# BuckConverter.net
KiCad netlist of a schematic drawn in Altium Designer
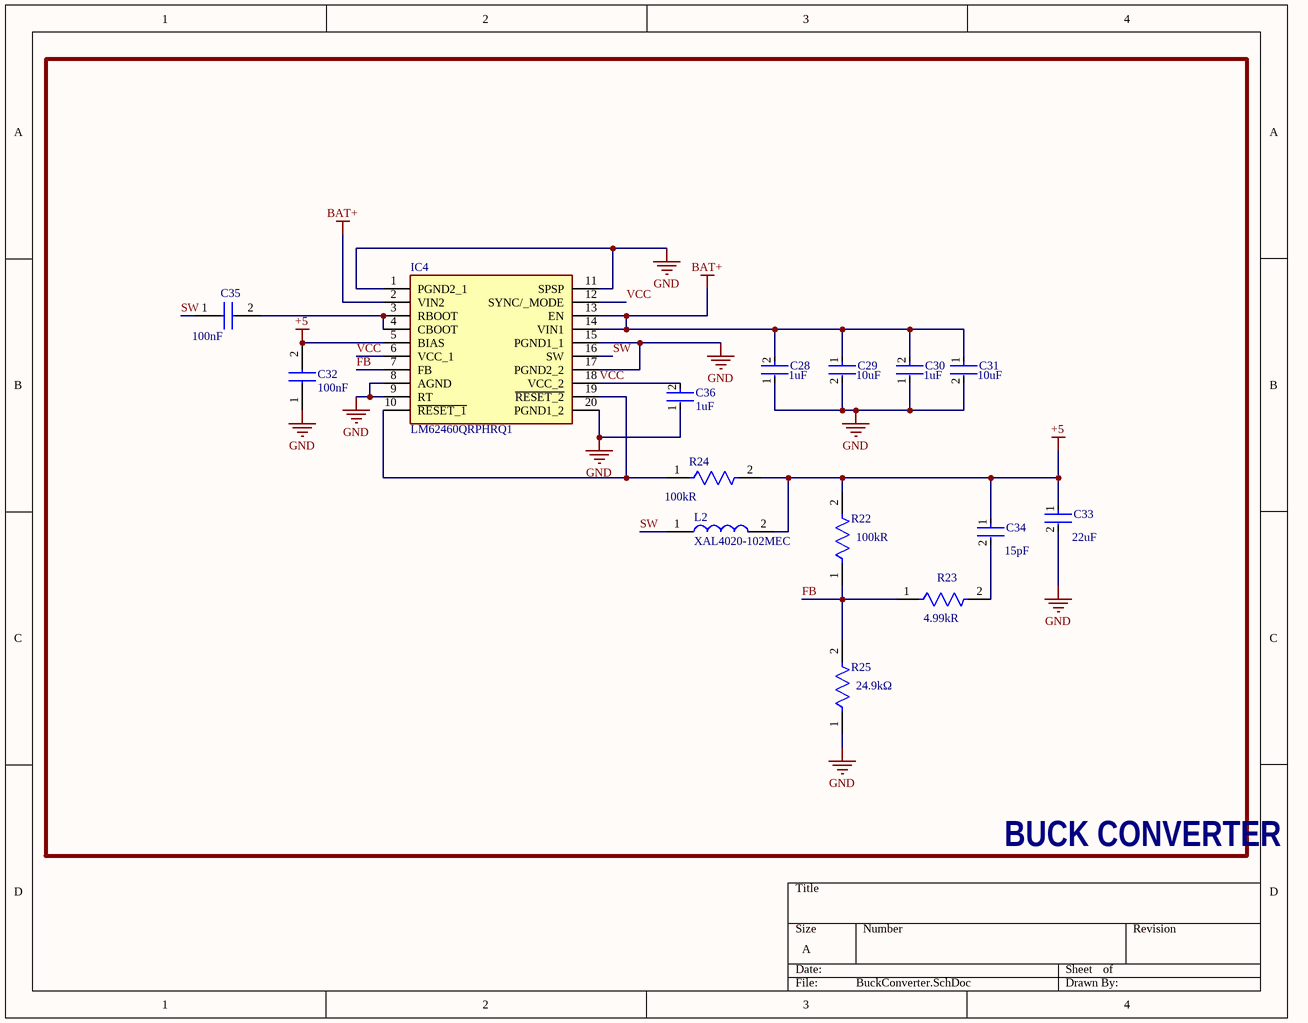
[diagram p0: BuckConverter.SchDoc]

(export (version "E")
  (design (tool "Eeschema 10.0.6"))
  (components
    (comp (ref "C28")
      (value "C1608X5R1H105K080AB")
      (footprint "FP-C1608-080-0_1-IPC_B")
      (description "Multilayer Ceramic Capacitors 1μF ±10% 50V X5R SMD 0603")
      (fields
        (field (name "VOLTAGE") "50V")
        (field (name "CAPACITANCE") "1uF")
        (field (name "TOLERANCE") "10%")
      )
      (libsource (lib "Altium Content Vault") (part "236180d848d6139a670b325ea6854c9"))
    )
    (comp (ref "C29")
      (value "GRM32ER71H106KA12L")
      (footprint "FP-GRM32-MFG")
      (description "CAP CER 10UF 50V X7R 1210")
      (fields
        (field (name "TOLERANCE") "10%")
        (field (name "MANUFACTURER") "Murata")
        (field (name "CAPACITANCE") "10uF")
      )
      (libsource (lib "Altium Content Vault") (part "11868f565c42a9108669ba33697ecf6"))
    )
    (comp (ref "C30")
      (value "C1608X5R1H105K080AB")
      (footprint "FP-C1608-080-0_1-IPC_B")
      (description "Multilayer Ceramic Capacitors 1μF ±10% 50V X5R SMD 0603")
      (fields
        (field (name "VOLTAGE") "50V")
        (field (name "CAPACITANCE") "1uF")
        (field (name "TOLERANCE") "10%")
      )
      (libsource (lib "Altium Content Vault") (part "236180d848d6139a670b325ea6854c9"))
    )
    (comp (ref "C31")
      (value "GRM32ER71H106KA12L")
      (footprint "FP-GRM32-MFG")
      (description "CAP CER 10UF 50V X7R 1210")
      (fields
        (field (name "TOLERANCE") "10%")
        (field (name "MANUFACTURER") "Murata")
        (field (name "CAPACITANCE") "10uF")
      )
      (libsource (lib "Altium Content Vault") (part "11868f565c42a9108669ba33697ecf6"))
    )
    (comp (ref "C32")
      (value "GRM155R71A104KA01D")
      (footprint "SamacSys:CAPC1005X55N")
      (description "Capacitor")
      (fields (field (name "MOUSER PART NUMBER") "81-GRM155R71A104KA1D") (field (name "CAPACITANCE") "100nF"))
      (libsource (lib "*") (part "GRM155R71A104KA01D"))
    )
    (comp (ref "C33")
      (value "GRM21BR61A226ME44L")
      (footprint "FP-GRM21B-0_2-e0_2_0_7-IPC_C")
      (description "Chip Multilayer Ceramic Capacitors for General Purpose, 0805, 22uF, X5R, 15%, 20%, 10V")
      (fields
        (field (name "TOLERANCE") "20%")
        (field (name "VOLTAGE") "10V")
        (field (name "CAPACITANCE") "22uF")
      )
      (libsource (lib "Altium Content Vault") (part "b4654b650e69147ec39a6b967a45e02"))
    )
    (comp (ref "C34")
      (value "CGA1A2C0G1E150J030BA")
      (footprint "FP-CGA1A-0_1-0_03-IPC_C")
      (description "Cap Ceramic 15pF 25V C0G 5% Pad SMD 0201 125°C Automotive T/R")
      (fields (field (name "TOLERANCE") "5%") (field (name "CAPACITANCE") "15pF"))
      (libsource (lib "Altium Content Vault") (part "b4654b650e69147ec39a6b967a45e02"))
    )
    (comp (ref "C35")
      (value "GRM155R71A104KA01D")
      (footprint "SamacSys:CAPC1005X55N")
      (description "Capacitor")
      (fields (field (name "MOUSER PART NUMBER") "81-GRM155R71A104KA1D") (field (name "CAPACITANCE") "100nF"))
      (libsource (lib "*") (part "GRM155R71A104KA01D"))
    )
    (comp (ref "C36")
      (value "GRM188R60J105KA01D")
      (footprint "FP-GRM188-0_1-MFG")
      (description "CAP CER 1UF 6.3V X5R 0603")
      (fields
        (field (name "CAPACITANCE") "1uF")
        (field (name "TOLERANCE") "10%")
        (field (name "VOLTAGE") "6.3V")
      )
      (libsource (lib "Altium Content Vault") (part "236180d848d6139a670b325ea6854c9"))
    )
    (comp (ref "IC4")
      (value "LM62460QRPHRQ1")
      (footprint "SamacSys:LM62460QRPHRQ1")
      (description "Integrated Circuit")
      (fields (field (name "MOUSER PART NUMBER") "595-LM62460QRPHRQ1"))
      (libsource (lib "*") (part "LM62460QRPHRQ1"))
    )
    (comp (ref "L2")
      (value "XAL4020-102MEC")
      (footprint "SamacSys:XAL40XX")
      (description "Inductor")
      (fields (field (name "MOUSER PART NUMBER") "994-XAL4020-102MEC"))
      (libsource (lib "*") (part "XAL4020-102MEC"))
    )
    (comp (ref "R22")
      (value "CRCW0402100KFKED")
      (footprint "FP-CRCW0402-e3-IPC_C")
      (description "RES Thick Film, 100kΩ, 1%, 0.063W, 100ppm/°C, 0402")
      (fields (field (name "RESISTANCE") "100kR") (field (name "TOLERANCE") "1%"))
      (libsource (lib "Altium Content Vault") (part "1029c3af85768c4190bb7ad29bc67b5"))
    )
    (comp (ref "R23")
      (value "CRCW04024K99FKED")
      (footprint "FP-CRCW0402-e3-MFG")
      (description "RES Thick Film, 4.99kΩ, 1%, 0.063W, 100ppm/°C, 0402")
      (fields (field (name "RESISTANCE") "4.99kR") (field (name "TOLERANCE") "1%"))
      (libsource (lib "Altium Content Vault") (part "1029c3af85768c4190bb7ad29bc67b5"))
    )
    (comp (ref "R24")
      (value "CRCW0402100KFKED")
      (footprint "FP-CRCW0402-e3-IPC_C")
      (description "RES Thick Film, 100kΩ, 1%, 0.063W, 100ppm/°C, 0402")
      (fields (field (name "RESISTANCE") "100kR") (field (name "TOLERANCE") "1%"))
      (libsource (lib "Altium Content Vault") (part "1029c3af85768c4190bb7ad29bc67b5"))
    )
    (comp (ref "R25")
      (value "RC0603FR-0724K9L")
      (footprint "FP-RC_L0603-MFG")
      (description "RES SMD 24.9K OHM 1% 1/10W 0603")
      (fields
        (field (name "VOLTAGE") "75V")
        (field (name "MANUFACTURER") "Yageo")
        (field (name "RESISTANCE") "24.9kΩ")
      )
      (libsource (lib "Altium Content Vault") (part "1029c3af85768c4190bb7ad29bc67b5"))
    )
  )
  (nets
    (net (code "1") (name "+5") (class "Default")
      (node (ref "C32") (pin "2") (pinfunction "2_2") (pintype "passive"))
      (node (ref "C33") (pin "1") (pinfunction "1_1") (pintype "passive"))
      (node (ref "C34") (pin "1") (pinfunction "1_1") (pintype "passive"))
      (node (ref "IC4") (pin "5") (pinfunction "BIAS_5") (pintype "passive"))
      (node (ref "L2") (pin "2") (pinfunction "2_2") (pintype "passive"))
      (node (ref "R22") (pin "2") (pinfunction "2_2") (pintype "passive"))
      (node (ref "R24") (pin "2") (pinfunction "2_2") (pintype "passive"))
    )
    (net (code "2") (name "/FB") (class "Default")
      (node (ref "IC4") (pin "7") (pinfunction "FB_7") (pintype "passive"))
      (node (ref "R22") (pin "1") (pinfunction "1_1") (pintype "passive"))
      (node (ref "R23") (pin "1") (pinfunction "1_1") (pintype "passive"))
      (node (ref "R25") (pin "2") (pinfunction "2_2") (pintype "passive"))
    )
    (net (code "3") (name "/SW") (class "Default")
      (node (ref "C35") (pin "1") (pinfunction "1_1") (pintype "passive"))
      (node (ref "IC4") (pin "16") (pinfunction "SW_16") (pintype "passive"))
      (node (ref "L2") (pin "1") (pinfunction "1_1") (pintype "passive"))
    )
    (net (code "4") (name "/VCC") (class "Default")
      (node (ref "C36") (pin "2") (pinfunction "2_2") (pintype "passive"))
      (node (ref "IC4") (pin "12") (pinfunction "SYNC/_MODE_12") (pintype "passive"))
      (node (ref "IC4") (pin "18") (pinfunction "VCC_2_18") (pintype "passive"))
      (node (ref "IC4") (pin "6") (pinfunction "VCC_1_6") (pintype "passive"))
    )
    (net (code "5") (name "BAT+") (class "Default")
      (node (ref "C28") (pin "2") (pinfunction "2_2") (pintype "passive"))
      (node (ref "C29") (pin "1") (pinfunction "1_1") (pintype "passive"))
      (node (ref "C30") (pin "2") (pinfunction "2_2") (pintype "passive"))
      (node (ref "C31") (pin "1") (pinfunction "1_1") (pintype "passive"))
      (node (ref "IC4") (pin "13") (pinfunction "EN_13") (pintype "passive"))
      (node (ref "IC4") (pin "14") (pinfunction "VIN1_14") (pintype "passive"))
      (node (ref "IC4") (pin "2") (pinfunction "VIN2_2") (pintype "passive"))
    )
    (net (code "6") (name "GND") (class "Default")
      (node (ref "C28") (pin "1") (pinfunction "1_1") (pintype "passive"))
      (node (ref "C29") (pin "2") (pinfunction "2_2") (pintype "passive"))
      (node (ref "C30") (pin "1") (pinfunction "1_1") (pintype "passive"))
      (node (ref "C31") (pin "2") (pinfunction "2_2") (pintype "passive"))
      (node (ref "C32") (pin "1") (pinfunction "1_1") (pintype "passive"))
      (node (ref "C33") (pin "2") (pinfunction "2_2") (pintype "passive"))
      (node (ref "C36") (pin "1") (pinfunction "1_1") (pintype "passive"))
      (node (ref "IC4") (pin "1") (pinfunction "PGND2_1_1") (pintype "passive"))
      (node (ref "IC4") (pin "11") (pinfunction "SPSP_11") (pintype "passive"))
      (node (ref "IC4") (pin "15") (pinfunction "PGND1_1_15") (pintype "passive"))
      (node (ref "IC4") (pin "17") (pinfunction "PGND2_2_17") (pintype "passive"))
      (node (ref "IC4") (pin "20") (pinfunction "PGND1_2_20") (pintype "passive"))
      (node (ref "IC4") (pin "8") (pinfunction "AGND_8") (pintype "passive"))
      (node (ref "IC4") (pin "9") (pinfunction "RT_9") (pintype "passive"))
      (node (ref "R25") (pin "1") (pinfunction "1_1") (pintype "passive"))
    )
    (net (code "7") (name "Net-(C34-Pad2)") (class "Default")
      (node (ref "C34") (pin "2") (pinfunction "2_2") (pintype "passive"))
      (node (ref "R23") (pin "2") (pinfunction "2_2") (pintype "passive"))
    )
    (net (code "8") (name "Net-(IC4-CBOOT)") (class "Default")
      (node (ref "C35") (pin "2") (pinfunction "2_2") (pintype "passive"))
      (node (ref "IC4") (pin "3") (pinfunction "RBOOT_3") (pintype "passive"))
      (node (ref "IC4") (pin "4") (pinfunction "CBOOT_4") (pintype "passive"))
    )
    (net (code "9") (name "Net-(IC4-~{RESET_1})") (class "Default")
      (node (ref "IC4") (pin "10") (pinfunction "~{RESET_1}_10") (pintype "passive"))
      (node (ref "IC4") (pin "19") (pinfunction "~{RESET_2}_19") (pintype "passive"))
      (node (ref "R24") (pin "1") (pinfunction "1_1") (pintype "passive"))
    )
  )
)
